# Motor_board.net
KiCad netlist of a schematic drawn in EAGLE
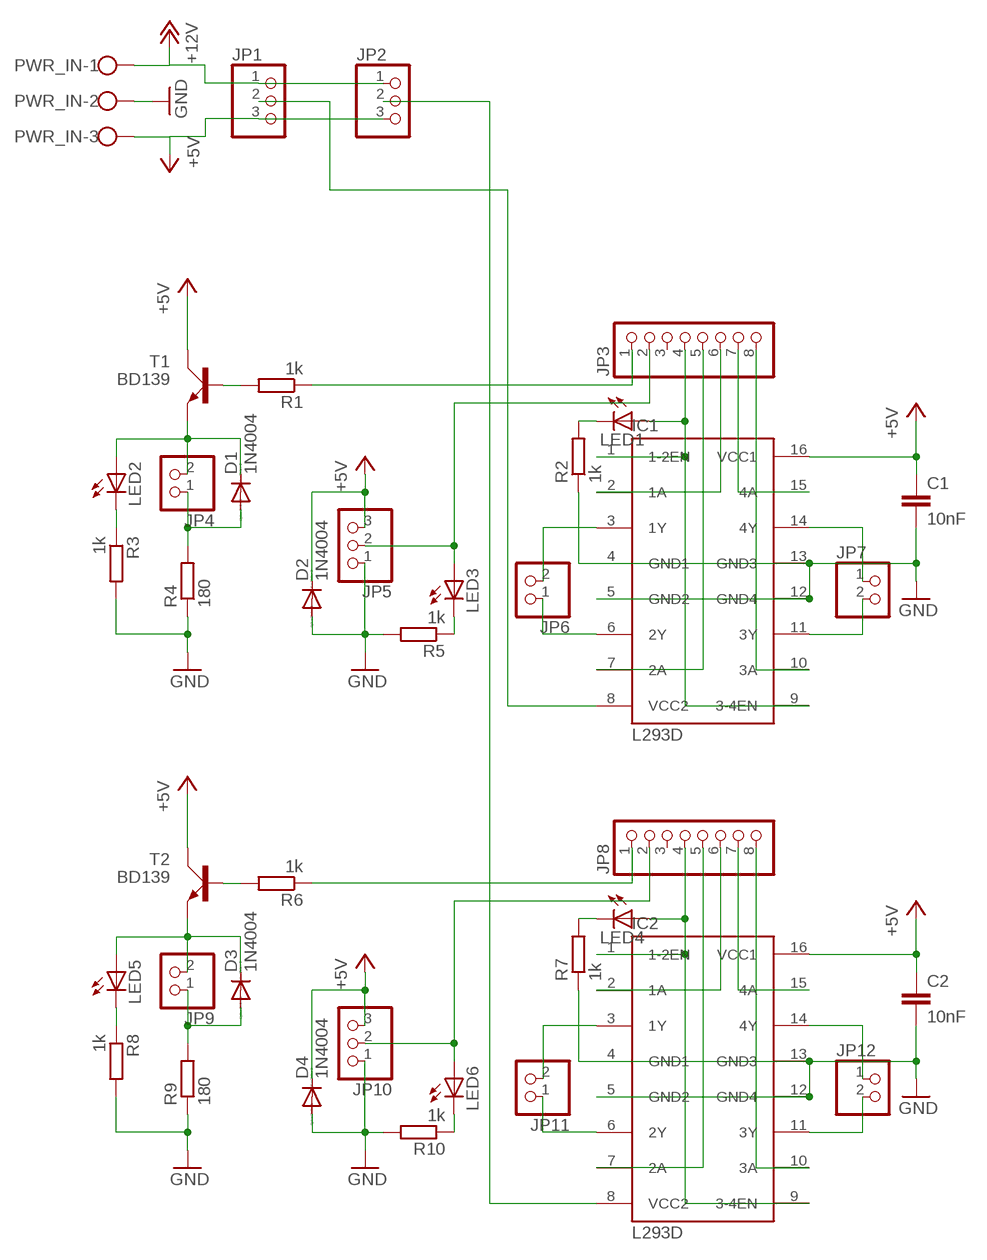
[diagram p0: schematic, sheet 1]

(export (version "E")
  (design (tool "Eeschema 10.0.6"))
  (components
    (comp (ref "C1")
      (value "10nF")
      (footprint "eagle-import:C050-024X044")
      (libsource (lib "eagle-import") (part "C-EU050-024X044"))
    )
    (comp (ref "C2")
      (value "10nF")
      (footprint "eagle-import:C050-024X044")
      (libsource (lib "eagle-import") (part "C-EU050-024X044"))
    )
    (comp (ref "D1")
      (value "1N4004")
      (footprint "eagle-import:DO41-10")
      (libsource (lib "eagle-import") (part "1N4004"))
    )
    (comp (ref "D2")
      (value "1N4004")
      (footprint "eagle-import:DO41-10")
      (libsource (lib "eagle-import") (part "1N4004"))
    )
    (comp (ref "D3")
      (value "1N4004")
      (footprint "eagle-import:DO41-10")
      (libsource (lib "eagle-import") (part "1N4004"))
    )
    (comp (ref "D4")
      (value "1N4004")
      (footprint "eagle-import:DO41-10")
      (libsource (lib "eagle-import") (part "1N4004"))
    )
    (comp (ref "IC1")
      (value "L293D")
      (footprint "eagle-import:DIL16")
      (libsource (lib "eagle-import") (part "L293D"))
    )
    (comp (ref "IC2")
      (value "L293D")
      (footprint "eagle-import:DIL16")
      (libsource (lib "eagle-import") (part "L293D"))
    )
    (comp (ref "JP1")
      (value "PINHD-1X3")
      (footprint "eagle-import:1X03")
      (libsource (lib "eagle-import") (part "PINHD-1X3"))
    )
    (comp (ref "JP2")
      (value "PINHD-1X3")
      (footprint "eagle-import:1X03")
      (libsource (lib "eagle-import") (part "PINHD-1X3"))
    )
    (comp (ref "JP3")
      (value "PINHD-1X8")
      (footprint "eagle-import:1X08")
      (libsource (lib "eagle-import") (part "PINHD-1X8"))
    )
    (comp (ref "JP4")
      (value "PINHD-1X2")
      (footprint "eagle-import:1X02")
      (libsource (lib "eagle-import") (part "PINHD-1X2"))
    )
    (comp (ref "JP5")
      (value "PINHD-1X3")
      (footprint "eagle-import:1X03")
      (libsource (lib "eagle-import") (part "PINHD-1X3"))
    )
    (comp (ref "JP6")
      (value "PINHD-1X2")
      (footprint "eagle-import:1X02")
      (libsource (lib "eagle-import") (part "PINHD-1X2"))
    )
    (comp (ref "JP7")
      (value "PINHD-1X2")
      (footprint "eagle-import:1X02")
      (libsource (lib "eagle-import") (part "PINHD-1X2"))
    )
    (comp (ref "JP8")
      (value "PINHD-1X8")
      (footprint "eagle-import:1X08")
      (libsource (lib "eagle-import") (part "PINHD-1X8"))
    )
    (comp (ref "JP9")
      (value "PINHD-1X2")
      (footprint "eagle-import:1X02")
      (libsource (lib "eagle-import") (part "PINHD-1X2"))
    )
    (comp (ref "JP10")
      (value "PINHD-1X3")
      (footprint "eagle-import:1X03")
      (libsource (lib "eagle-import") (part "PINHD-1X3"))
    )
    (comp (ref "JP11")
      (value "PINHD-1X2")
      (footprint "eagle-import:1X02")
      (libsource (lib "eagle-import") (part "PINHD-1X2"))
    )
    (comp (ref "JP12")
      (value "PINHD-1X2")
      (footprint "eagle-import:1X02")
      (libsource (lib "eagle-import") (part "PINHD-1X2"))
    )
    (comp (ref "LED1")
      (value "LED3MM")
      (footprint "eagle-import:LED3MM")
      (libsource (lib "eagle-import") (part "LED3MM"))
    )
    (comp (ref "LED2")
      (value "LED3MM")
      (footprint "eagle-import:LED3MM")
      (libsource (lib "eagle-import") (part "LED3MM"))
    )
    (comp (ref "LED3")
      (value "LED3MM")
      (footprint "eagle-import:LED3MM")
      (libsource (lib "eagle-import") (part "LED3MM"))
    )
    (comp (ref "LED4")
      (value "LED3MM")
      (footprint "eagle-import:LED3MM")
      (libsource (lib "eagle-import") (part "LED3MM"))
    )
    (comp (ref "LED5")
      (value "LED3MM")
      (footprint "eagle-import:LED3MM")
      (libsource (lib "eagle-import") (part "LED3MM"))
    )
    (comp (ref "LED6")
      (value "LED3MM")
      (footprint "eagle-import:LED3MM")
      (libsource (lib "eagle-import") (part "LED3MM"))
    )
    (comp (ref "PWR_IN")
      (value "W237-103")
      (footprint "eagle-import:W237-103")
      (fields (field (name "MPN") "237-103"))
      (libsource (lib "eagle-import") (part "W237-103"))
    )
    (comp (ref "R1")
      (value "1k")
      (footprint "eagle-import:0207_7")
      (libsource (lib "eagle-import") (part "R-EU_0207/7"))
    )
    (comp (ref "R2")
      (value "1k")
      (footprint "eagle-import:0207_7")
      (libsource (lib "eagle-import") (part "R-EU_0207/7"))
    )
    (comp (ref "R3")
      (value "1k")
      (footprint "eagle-import:0207_7")
      (libsource (lib "eagle-import") (part "R-EU_0207/7"))
    )
    (comp (ref "R4")
      (value "180")
      (footprint "eagle-import:0414V")
      (libsource (lib "eagle-import") (part "R-EU_0414/5V"))
    )
    (comp (ref "R5")
      (value "1k")
      (footprint "eagle-import:0207_7")
      (libsource (lib "eagle-import") (part "R-EU_0207/7"))
    )
    (comp (ref "R6")
      (value "1k")
      (footprint "eagle-import:0207_7")
      (libsource (lib "eagle-import") (part "R-EU_0207/7"))
    )
    (comp (ref "R7")
      (value "1k")
      (footprint "eagle-import:0207_7")
      (libsource (lib "eagle-import") (part "R-EU_0207/7"))
    )
    (comp (ref "R8")
      (value "1k")
      (footprint "eagle-import:0207_7")
      (libsource (lib "eagle-import") (part "R-EU_0207/7"))
    )
    (comp (ref "R9")
      (value "180")
      (footprint "eagle-import:0414V")
      (libsource (lib "eagle-import") (part "R-EU_0414/5V"))
    )
    (comp (ref "R10")
      (value "1k")
      (footprint "eagle-import:0207_7")
      (libsource (lib "eagle-import") (part "R-EU_0207/7"))
    )
    (comp (ref "T1")
      (value "BD139")
      (footprint "eagle-import:TO126AV")
      (libsource (lib "eagle-import") (part "BD139"))
    )
    (comp (ref "T2")
      (value "BD139")
      (footprint "eagle-import:TO126AV")
      (libsource (lib "eagle-import") (part "BD139"))
    )
  )
  (nets
    (net (code "1") (name "+5V") (class "Default")
      (node (ref "C1") (pin "1") (pinfunction "1_1") (pintype "passive"))
      (node (ref "C2") (pin "1") (pinfunction "1_1") (pintype "passive"))
      (node (ref "D2") (pin "C") (pinfunction "C_C") (pintype "passive"))
      (node (ref "D4") (pin "C") (pinfunction "C_C") (pintype "passive"))
      (node (ref "IC1") (pin "16") (pinfunction "VCC1_16") (pintype "power_in"))
      (node (ref "IC2") (pin "16") (pinfunction "VCC1_16") (pintype "power_in"))
      (node (ref "JP1") (pin "3") (pinfunction "3_3") (pintype "passive"))
      (node (ref "JP10") (pin "3") (pinfunction "3_3") (pintype "passive"))
      (node (ref "JP2") (pin "3") (pinfunction "3_3") (pintype "passive"))
      (node (ref "JP5") (pin "3") (pinfunction "3_3") (pintype "passive"))
      (node (ref "PWR_IN") (pin "3") (pinfunction "KL_3") (pintype "passive"))
      (node (ref "T1") (pin "C") (pinfunction "C_C") (pintype "passive"))
      (node (ref "T2") (pin "C") (pinfunction "C_C") (pintype "passive"))
    )
    (net (code "2") (name "+12V") (class "Default")
      (node (ref "JP1") (pin "1") (pinfunction "1_1") (pintype "passive"))
      (node (ref "JP2") (pin "1") (pinfunction "1_1") (pintype "passive"))
      (node (ref "PWR_IN") (pin "1") (pinfunction "KL_1") (pintype "passive"))
    )
    (net (code "3") (name "GND") (class "Default")
      (node (ref "C1") (pin "2") (pinfunction "2_2") (pintype "passive"))
      (node (ref "C2") (pin "2") (pinfunction "2_2") (pintype "passive"))
      (node (ref "D2") (pin "A") (pinfunction "A_A") (pintype "passive"))
      (node (ref "D4") (pin "A") (pinfunction "A_A") (pintype "passive"))
      (node (ref "IC1") (pin "12") (pinfunction "GND4_12") (pintype "power_in"))
      (node (ref "IC1") (pin "13") (pinfunction "GND3_13") (pintype "power_in"))
      (node (ref "IC1") (pin "4") (pinfunction "GND1_4") (pintype "power_in"))
      (node (ref "IC1") (pin "5") (pinfunction "GND2_5") (pintype "power_in"))
      (node (ref "IC2") (pin "12") (pinfunction "GND4_12") (pintype "power_in"))
      (node (ref "IC2") (pin "13") (pinfunction "GND3_13") (pintype "power_in"))
      (node (ref "IC2") (pin "4") (pinfunction "GND1_4") (pintype "power_in"))
      (node (ref "IC2") (pin "5") (pinfunction "GND2_5") (pintype "power_in"))
      (node (ref "JP10") (pin "1") (pinfunction "1_1") (pintype "passive"))
      (node (ref "JP5") (pin "1") (pinfunction "1_1") (pintype "passive"))
      (node (ref "PWR_IN") (pin "2") (pinfunction "KL_2") (pintype "passive"))
      (node (ref "R10") (pin "2") (pinfunction "2_2") (pintype "passive"))
      (node (ref "R2") (pin "1") (pinfunction "1_1") (pintype "passive"))
      (node (ref "R3") (pin "2") (pinfunction "2_2") (pintype "passive"))
      (node (ref "R4") (pin "1") (pinfunction "1_1") (pintype "passive"))
      (node (ref "R5") (pin "2") (pinfunction "2_2") (pintype "passive"))
      (node (ref "R7") (pin "1") (pinfunction "1_1") (pintype "passive"))
      (node (ref "R8") (pin "2") (pinfunction "2_2") (pintype "passive"))
      (node (ref "R9") (pin "1") (pinfunction "1_1") (pintype "passive"))
    )
    (net (code "4") (name "Net-(D1-PadA)") (class "Default")
      (node (ref "D1") (pin "A") (pinfunction "A_A") (pintype "passive"))
      (node (ref "JP4") (pin "1") (pinfunction "1_1") (pintype "passive"))
      (node (ref "R4") (pin "2") (pinfunction "2_2") (pintype "passive"))
    )
    (net (code "5") (name "Net-(D1-PadC)") (class "Default")
      (node (ref "D1") (pin "C") (pinfunction "C_C") (pintype "passive"))
      (node (ref "JP4") (pin "2") (pinfunction "2_2") (pintype "passive"))
      (node (ref "LED2") (pin "A") (pinfunction "A_A") (pintype "passive"))
      (node (ref "T1") (pin "E") (pinfunction "E_E") (pintype "passive"))
    )
    (net (code "6") (name "Net-(D3-PadA)") (class "Default")
      (node (ref "D3") (pin "A") (pinfunction "A_A") (pintype "passive"))
      (node (ref "JP9") (pin "1") (pinfunction "1_1") (pintype "passive"))
      (node (ref "R9") (pin "2") (pinfunction "2_2") (pintype "passive"))
    )
    (net (code "7") (name "Net-(D3-PadC)") (class "Default")
      (node (ref "D3") (pin "C") (pinfunction "C_C") (pintype "passive"))
      (node (ref "JP9") (pin "2") (pinfunction "2_2") (pintype "passive"))
      (node (ref "LED5") (pin "A") (pinfunction "A_A") (pintype "passive"))
      (node (ref "T2") (pin "E") (pinfunction "E_E") (pintype "passive"))
    )
    (net (code "8") (name "Net-(IC1-1-2EN)") (class "Default")
      (node (ref "IC1") (pin "1") (pinfunction "1-2EN_1") (pintype "input"))
      (node (ref "IC1") (pin "9") (pinfunction "3-4EN_9") (pintype "input"))
      (node (ref "JP3") (pin "4") (pinfunction "4_4") (pintype "passive"))
      (node (ref "LED1") (pin "A") (pinfunction "A_A") (pintype "passive"))
    )
    (net (code "9") (name "Net-(IC1-1A)") (class "Default")
      (node (ref "IC1") (pin "2") (pinfunction "1A_2") (pintype "input"))
      (node (ref "JP3") (pin "6") (pinfunction "6_6") (pintype "passive"))
    )
    (net (code "10") (name "Net-(IC1-1Y)") (class "Default")
      (node (ref "IC1") (pin "3") (pinfunction "1Y_3") (pintype "output"))
      (node (ref "JP6") (pin "2") (pinfunction "2_2") (pintype "passive"))
    )
    (net (code "11") (name "Net-(IC1-2A)") (class "Default")
      (node (ref "IC1") (pin "7") (pinfunction "2A_7") (pintype "input"))
      (node (ref "JP3") (pin "5") (pinfunction "5_5") (pintype "passive"))
    )
    (net (code "12") (name "Net-(IC1-2Y)") (class "Default")
      (node (ref "IC1") (pin "6") (pinfunction "2Y_6") (pintype "output"))
      (node (ref "JP6") (pin "1") (pinfunction "1_1") (pintype "passive"))
    )
    (net (code "13") (name "Net-(IC1-3A)") (class "Default")
      (node (ref "IC1") (pin "10") (pinfunction "3A_10") (pintype "input"))
      (node (ref "JP3") (pin "8") (pinfunction "8_8") (pintype "passive"))
    )
    (net (code "14") (name "Net-(IC1-3Y)") (class "Default")
      (node (ref "IC1") (pin "11") (pinfunction "3Y_11") (pintype "output"))
      (node (ref "JP7") (pin "2") (pinfunction "2_2") (pintype "passive"))
    )
    (net (code "15") (name "Net-(IC1-4A)") (class "Default")
      (node (ref "IC1") (pin "15") (pinfunction "4A_15") (pintype "input"))
      (node (ref "JP3") (pin "7") (pinfunction "7_7") (pintype "passive"))
    )
    (net (code "16") (name "Net-(IC1-4Y)") (class "Default")
      (node (ref "IC1") (pin "14") (pinfunction "4Y_14") (pintype "output"))
      (node (ref "JP7") (pin "1") (pinfunction "1_1") (pintype "passive"))
    )
    (net (code "17") (name "Net-(IC1-VCC2)") (class "Default")
      (node (ref "IC1") (pin "8") (pinfunction "VCC2_8") (pintype "power_in"))
      (node (ref "JP1") (pin "2") (pinfunction "2_2") (pintype "passive"))
    )
    (net (code "18") (name "Net-(IC2-1-2EN)") (class "Default")
      (node (ref "IC2") (pin "1") (pinfunction "1-2EN_1") (pintype "input"))
      (node (ref "IC2") (pin "9") (pinfunction "3-4EN_9") (pintype "input"))
      (node (ref "JP8") (pin "4") (pinfunction "4_4") (pintype "passive"))
      (node (ref "LED4") (pin "A") (pinfunction "A_A") (pintype "passive"))
    )
    (net (code "19") (name "Net-(IC2-1A)") (class "Default")
      (node (ref "IC2") (pin "2") (pinfunction "1A_2") (pintype "input"))
      (node (ref "JP8") (pin "6") (pinfunction "6_6") (pintype "passive"))
    )
    (net (code "20") (name "Net-(IC2-1Y)") (class "Default")
      (node (ref "IC2") (pin "3") (pinfunction "1Y_3") (pintype "output"))
      (node (ref "JP11") (pin "2") (pinfunction "2_2") (pintype "passive"))
    )
    (net (code "21") (name "Net-(IC2-2A)") (class "Default")
      (node (ref "IC2") (pin "7") (pinfunction "2A_7") (pintype "input"))
      (node (ref "JP8") (pin "5") (pinfunction "5_5") (pintype "passive"))
    )
    (net (code "22") (name "Net-(IC2-2Y)") (class "Default")
      (node (ref "IC2") (pin "6") (pinfunction "2Y_6") (pintype "output"))
      (node (ref "JP11") (pin "1") (pinfunction "1_1") (pintype "passive"))
    )
    (net (code "23") (name "Net-(IC2-3A)") (class "Default")
      (node (ref "IC2") (pin "10") (pinfunction "3A_10") (pintype "input"))
      (node (ref "JP8") (pin "8") (pinfunction "8_8") (pintype "passive"))
    )
    (net (code "24") (name "Net-(IC2-3Y)") (class "Default")
      (node (ref "IC2") (pin "11") (pinfunction "3Y_11") (pintype "output"))
      (node (ref "JP12") (pin "2") (pinfunction "2_2") (pintype "passive"))
    )
    (net (code "25") (name "Net-(IC2-4A)") (class "Default")
      (node (ref "IC2") (pin "15") (pinfunction "4A_15") (pintype "input"))
      (node (ref "JP8") (pin "7") (pinfunction "7_7") (pintype "passive"))
    )
    (net (code "26") (name "Net-(IC2-4Y)") (class "Default")
      (node (ref "IC2") (pin "14") (pinfunction "4Y_14") (pintype "output"))
      (node (ref "JP12") (pin "1") (pinfunction "1_1") (pintype "passive"))
    )
    (net (code "27") (name "Net-(IC2-VCC2)") (class "Default")
      (node (ref "IC2") (pin "8") (pinfunction "VCC2_8") (pintype "power_in"))
      (node (ref "JP2") (pin "2") (pinfunction "2_2") (pintype "passive"))
    )
    (net (code "28") (name "Net-(JP3-Pad1)") (class "Default")
      (node (ref "JP3") (pin "1") (pinfunction "1_1") (pintype "passive"))
      (node (ref "R1") (pin "1") (pinfunction "1_1") (pintype "passive"))
    )
    (net (code "29") (name "Net-(JP3-Pad2)") (class "Default")
      (node (ref "JP3") (pin "2") (pinfunction "2_2") (pintype "passive"))
      (node (ref "JP5") (pin "2") (pinfunction "2_2") (pintype "passive"))
      (node (ref "LED3") (pin "A") (pinfunction "A_A") (pintype "passive"))
    )
    (net (code "30") (name "Net-(JP8-Pad1)") (class "Default")
      (node (ref "JP8") (pin "1") (pinfunction "1_1") (pintype "passive"))
      (node (ref "R6") (pin "1") (pinfunction "1_1") (pintype "passive"))
    )
    (net (code "31") (name "Net-(JP10-Pad2)") (class "Default")
      (node (ref "JP10") (pin "2") (pinfunction "2_2") (pintype "passive"))
      (node (ref "JP8") (pin "2") (pinfunction "2_2") (pintype "passive"))
      (node (ref "LED6") (pin "A") (pinfunction "A_A") (pintype "passive"))
    )
    (net (code "32") (name "Net-(LED1-C)") (class "Default")
      (node (ref "LED1") (pin "K") (pinfunction "C_K") (pintype "passive"))
      (node (ref "R2") (pin "2") (pinfunction "2_2") (pintype "passive"))
    )
    (net (code "33") (name "Net-(LED2-C)") (class "Default")
      (node (ref "LED2") (pin "K") (pinfunction "C_K") (pintype "passive"))
      (node (ref "R3") (pin "1") (pinfunction "1_1") (pintype "passive"))
    )
    (net (code "34") (name "Net-(LED3-C)") (class "Default")
      (node (ref "LED3") (pin "K") (pinfunction "C_K") (pintype "passive"))
      (node (ref "R5") (pin "1") (pinfunction "1_1") (pintype "passive"))
    )
    (net (code "35") (name "Net-(LED4-C)") (class "Default")
      (node (ref "LED4") (pin "K") (pinfunction "C_K") (pintype "passive"))
      (node (ref "R7") (pin "2") (pinfunction "2_2") (pintype "passive"))
    )
    (net (code "36") (name "Net-(LED5-C)") (class "Default")
      (node (ref "LED5") (pin "K") (pinfunction "C_K") (pintype "passive"))
      (node (ref "R8") (pin "1") (pinfunction "1_1") (pintype "passive"))
    )
    (net (code "37") (name "Net-(LED6-C)") (class "Default")
      (node (ref "LED6") (pin "K") (pinfunction "C_K") (pintype "passive"))
      (node (ref "R10") (pin "1") (pinfunction "1_1") (pintype "passive"))
    )
    (net (code "38") (name "Net-(R1-Pad2)") (class "Default")
      (node (ref "R1") (pin "2") (pinfunction "2_2") (pintype "passive"))
      (node (ref "T1") (pin "B") (pinfunction "B_B") (pintype "passive"))
    )
    (net (code "39") (name "Net-(R6-Pad2)") (class "Default")
      (node (ref "R6") (pin "2") (pinfunction "2_2") (pintype "passive"))
      (node (ref "T2") (pin "B") (pinfunction "B_B") (pintype "passive"))
    )
    (net (code "40") (name "unconnected-(JP3-Pad3)") (class "Default")
      (node (ref "JP3") (pin "3") (pinfunction "3_3") (pintype "passive"))
    )
    (net (code "41") (name "unconnected-(JP8-Pad3)") (class "Default")
      (node (ref "JP8") (pin "3") (pinfunction "3_3") (pintype "passive"))
    )
  )
)
